# design.net
KiCad netlist of a schematic drawn in EasyEDA
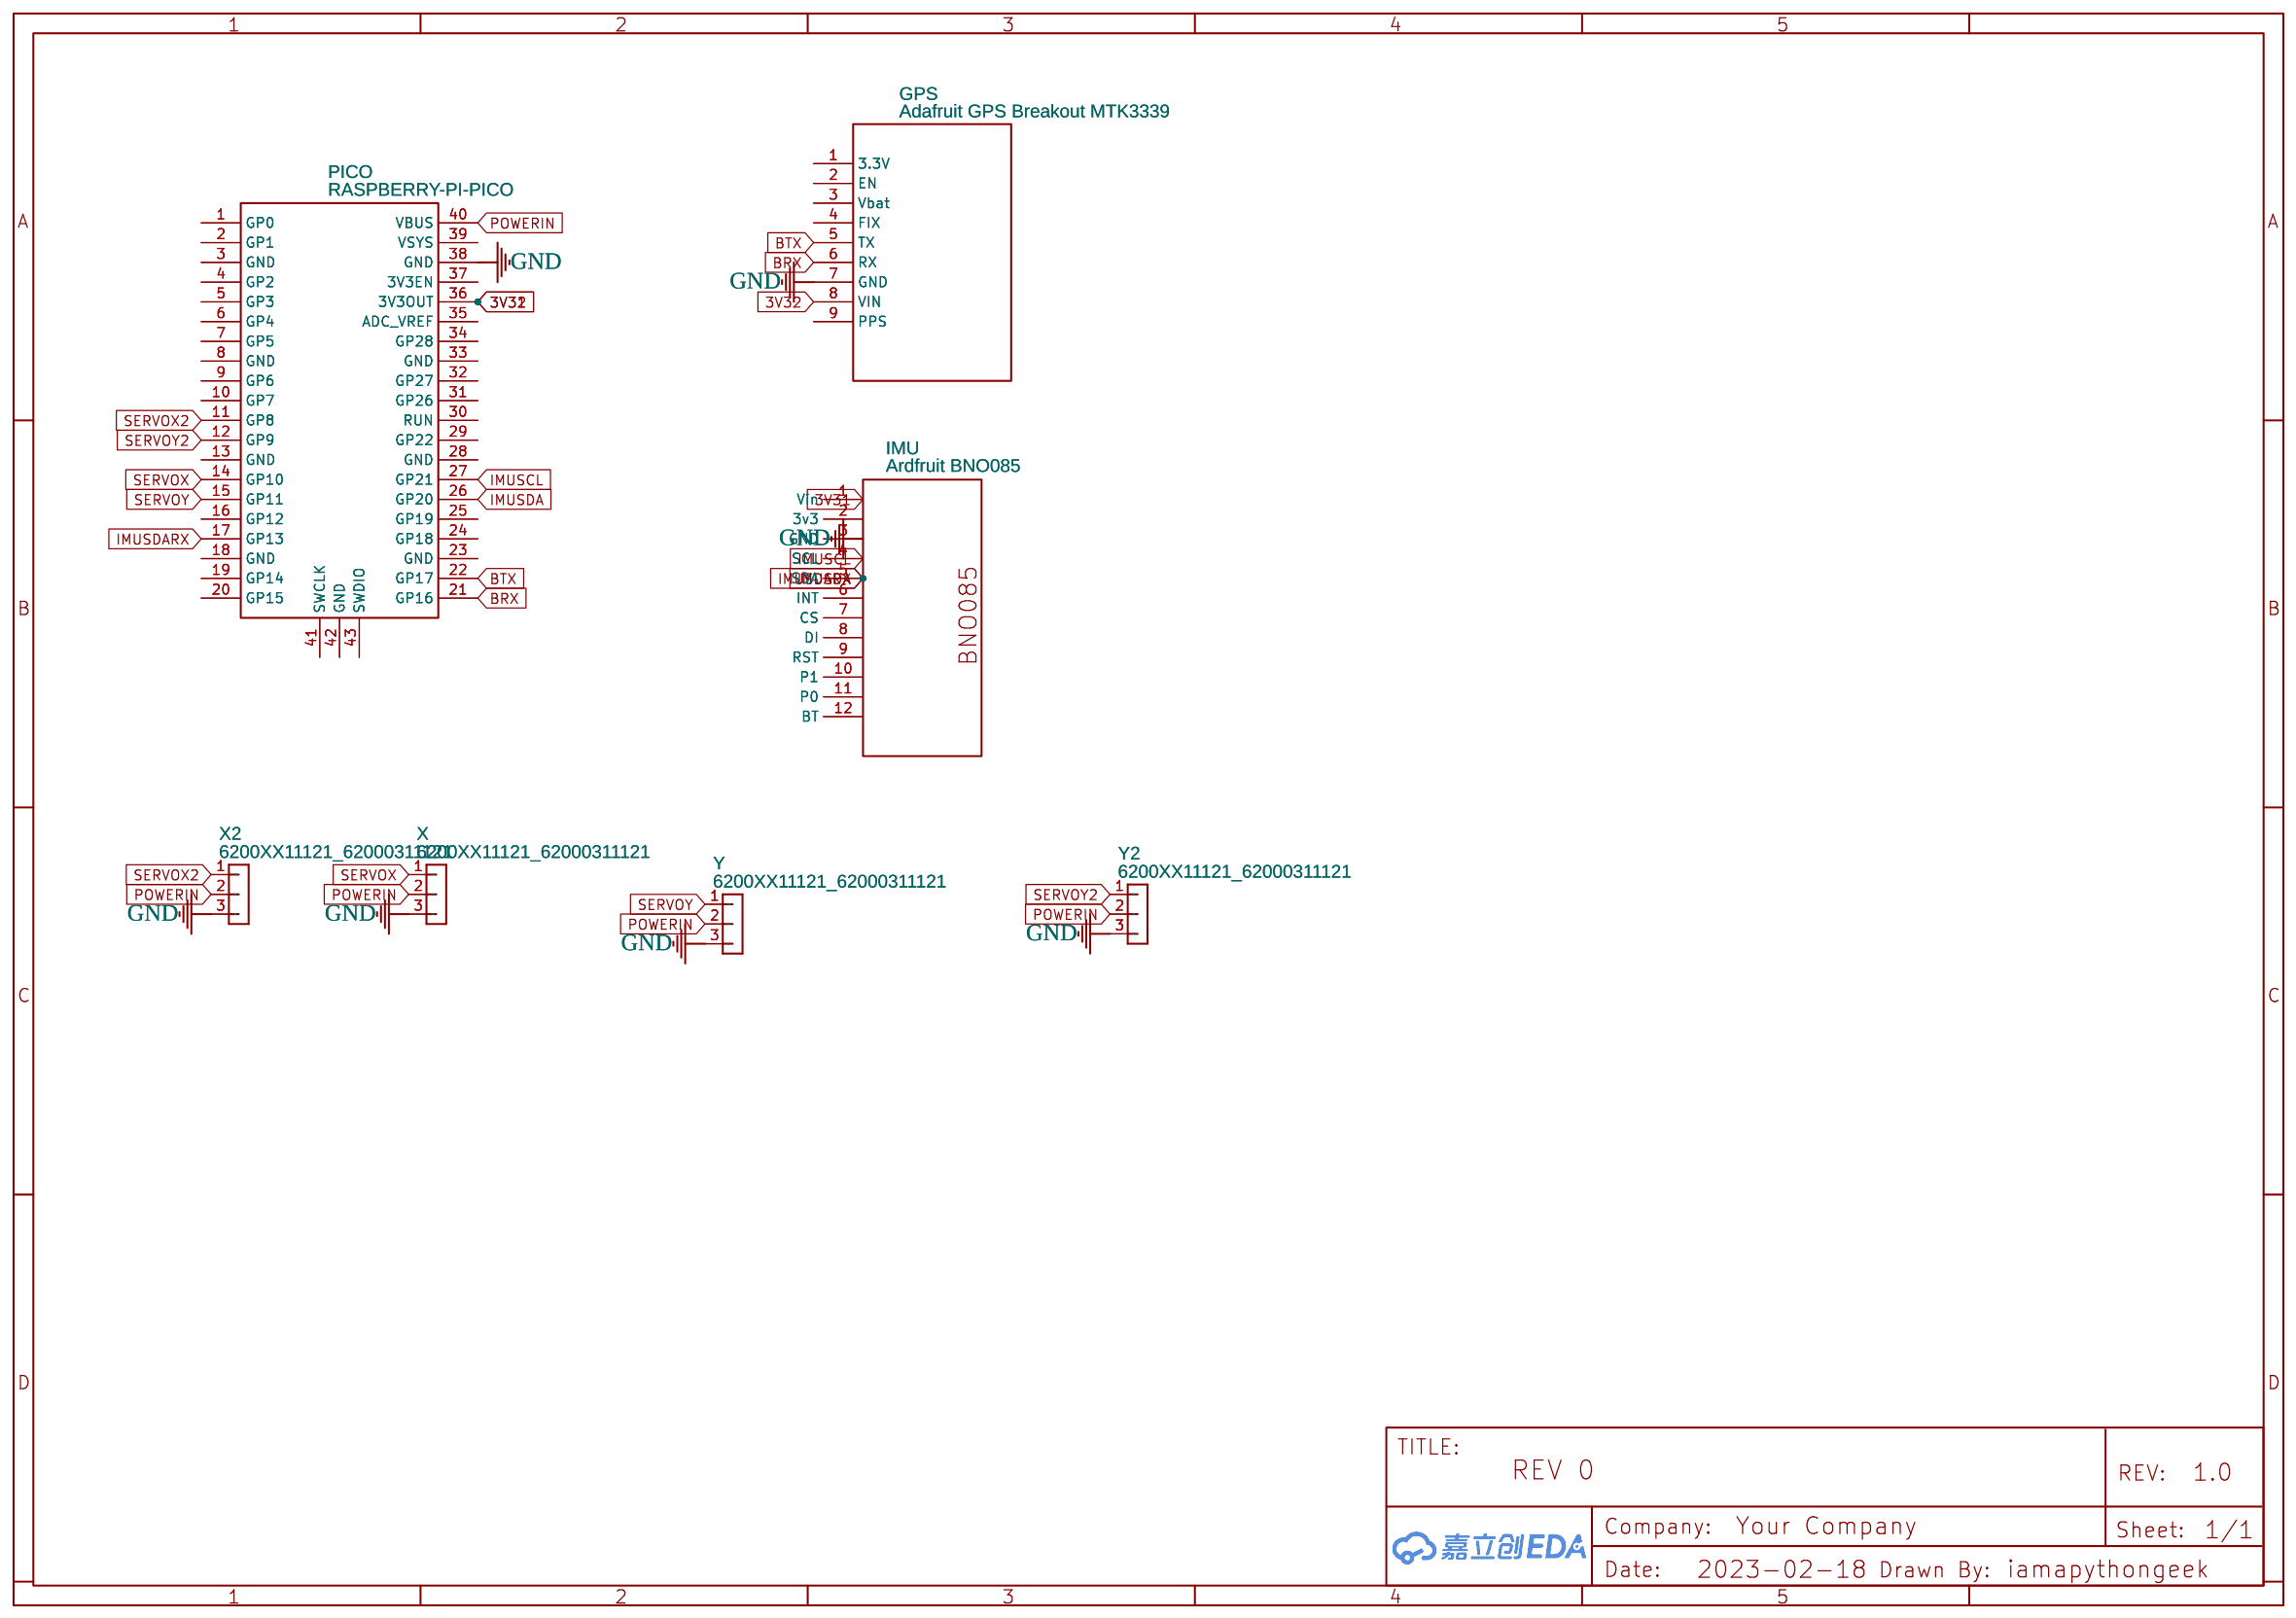
[diagram p0: schematic sheet]

(export (version "E")
  (design (tool "Eeschema 10.0.6"))
  (components
    (comp (ref "GPS")
      (value "Adafruit GPS Breakout MTK3339")
      (libsource (lib "") (part "Adafruit GPS Breakout MTK3339"))
    )
    (comp (ref "IMU") (value "Ardfruit BNO085") (libsource (lib "") (part "Ardfruit BNO085")))
    (comp (ref "PICO") (value "RASPBERRY-PI-PICO") (libsource (lib "") (part "RASPBERRY-PI-PICO")))
    (comp (ref "X") (value "6200XX11121_62000311121") (libsource (lib "") (part "6200XX11121_62000311121")))
    (comp (ref "X2") (value "6200XX11121_62000311121") (libsource (lib "") (part "6200XX11121_62000311121")))
    (comp (ref "Y") (value "6200XX11121_62000311121") (libsource (lib "") (part "6200XX11121_62000311121_1")))
    (comp (ref "Y2")
      (value "6200XX11121_62000311121")
      (libsource (lib "") (part "6200XX11121_62000311121_1"))
    )
  )
  (nets
    (net (code "1") (name "3V31") (class "Default")
      (node (ref "GPS") (pin "8") (pinfunction "VIN_8") (pintype "unspecified"))
      (node (ref "IMU") (pin "1") (pinfunction "Vin_1") (pintype "unspecified"))
      (node (ref "PICO") (pin "36") (pinfunction "3V3OUT_36") (pintype "unspecified"))
    )
    (net (code "2") (name "BRX") (class "Default")
      (node (ref "GPS") (pin "6") (pinfunction "RX_6") (pintype "unspecified"))
      (node (ref "PICO") (pin "21") (pinfunction "GP16_21") (pintype "unspecified"))
    )
    (net (code "3") (name "BTX") (class "Default")
      (node (ref "GPS") (pin "5") (pinfunction "TX_5") (pintype "unspecified"))
      (node (ref "PICO") (pin "22") (pinfunction "GP17_22") (pintype "unspecified"))
    )
    (net (code "4") (name "GND") (class "Default")
      (node (ref "GPS") (pin "7") (pinfunction "GND_7") (pintype "unspecified"))
      (node (ref "IMU") (pin "3") (pinfunction "GND_3") (pintype "unspecified"))
      (node (ref "PICO") (pin "38") (pinfunction "GND_38") (pintype "unspecified"))
      (node (ref "X") (pin "3") (pinfunction "3_3") (pintype "bidirectional"))
      (node (ref "X2") (pin "3") (pinfunction "3_3") (pintype "bidirectional"))
      (node (ref "Y") (pin "3") (pinfunction "3_3") (pintype "bidirectional"))
      (node (ref "Y2") (pin "3") (pinfunction "3_3") (pintype "bidirectional"))
    )
    (net (code "5") (name "IMUSCL") (class "Default")
      (node (ref "IMU") (pin "4") (pinfunction "SCL_4") (pintype "unspecified"))
      (node (ref "PICO") (pin "27") (pinfunction "GP21_27") (pintype "unspecified"))
    )
    (net (code "6") (name "IMUSDA") (class "Default")
      (node (ref "IMU") (pin "5") (pinfunction "SDA_5") (pintype "unspecified"))
      (node (ref "PICO") (pin "17") (pinfunction "GP13_17") (pintype "unspecified"))
      (node (ref "PICO") (pin "26") (pinfunction "GP20_26") (pintype "unspecified"))
    )
    (net (code "7") (name "POWERIN") (class "Default")
      (node (ref "PICO") (pin "40") (pinfunction "VBUS_40") (pintype "unspecified"))
      (node (ref "X") (pin "2") (pinfunction "2_2") (pintype "bidirectional"))
      (node (ref "X2") (pin "2") (pinfunction "2_2") (pintype "bidirectional"))
      (node (ref "Y") (pin "2") (pinfunction "2_2") (pintype "bidirectional"))
      (node (ref "Y2") (pin "2") (pinfunction "2_2") (pintype "bidirectional"))
    )
    (net (code "8") (name "SERVOX") (class "Default")
      (node (ref "PICO") (pin "14") (pinfunction "GP10_14") (pintype "unspecified"))
      (node (ref "X") (pin "1") (pinfunction "1_1") (pintype "bidirectional"))
    )
    (net (code "9") (name "SERVOX2") (class "Default")
      (node (ref "PICO") (pin "11") (pinfunction "GP8_11") (pintype "unspecified"))
      (node (ref "X2") (pin "1") (pinfunction "1_1") (pintype "bidirectional"))
    )
    (net (code "10") (name "SERVOY") (class "Default")
      (node (ref "PICO") (pin "15") (pinfunction "GP11_15") (pintype "unspecified"))
      (node (ref "Y") (pin "1") (pinfunction "1_1") (pintype "bidirectional"))
    )
    (net (code "11") (name "SERVOY2") (class "Default")
      (node (ref "PICO") (pin "12") (pinfunction "GP9_12") (pintype "unspecified"))
      (node (ref "Y2") (pin "1") (pinfunction "1_1") (pintype "bidirectional"))
    )
    (net (code "12") (name "unconnected-(GPS-3.3V-Pad1)") (class "Default")
      (node (ref "GPS") (pin "1") (pinfunction "3.3V_1") (pintype "unspecified"))
    )
    (net (code "13") (name "unconnected-(GPS-EN-Pad2)") (class "Default")
      (node (ref "GPS") (pin "2") (pinfunction "EN_2") (pintype "unspecified"))
    )
    (net (code "14") (name "unconnected-(GPS-FIX-Pad4)") (class "Default")
      (node (ref "GPS") (pin "4") (pinfunction "FIX_4") (pintype "unspecified"))
    )
    (net (code "15") (name "unconnected-(GPS-PPS-Pad9)") (class "Default")
      (node (ref "GPS") (pin "9") (pinfunction "PPS_9") (pintype "unspecified"))
    )
    (net (code "16") (name "unconnected-(GPS-Vbat-Pad3)") (class "Default")
      (node (ref "GPS") (pin "3") (pinfunction "Vbat_3") (pintype "unspecified"))
    )
    (net (code "17") (name "unconnected-(IMU-3v3-Pad2)") (class "Default")
      (node (ref "IMU") (pin "2") (pinfunction "3v3_2") (pintype "unspecified"))
    )
    (net (code "18") (name "unconnected-(IMU-BT-Pad12)") (class "Default")
      (node (ref "IMU") (pin "12") (pinfunction "BT_12") (pintype "unspecified"))
    )
    (net (code "19") (name "unconnected-(IMU-CS-Pad7)") (class "Default")
      (node (ref "IMU") (pin "7") (pinfunction "CS_7") (pintype "unspecified"))
    )
    (net (code "20") (name "unconnected-(IMU-DI-Pad8)") (class "Default")
      (node (ref "IMU") (pin "8") (pinfunction "DI_8") (pintype "unspecified"))
    )
    (net (code "21") (name "unconnected-(IMU-INT-Pad6)") (class "Default")
      (node (ref "IMU") (pin "6") (pinfunction "INT_6") (pintype "unspecified"))
    )
    (net (code "22") (name "unconnected-(IMU-P0-Pad11)") (class "Default")
      (node (ref "IMU") (pin "11") (pinfunction "P0_11") (pintype "unspecified"))
    )
    (net (code "23") (name "unconnected-(IMU-P1-Pad10)") (class "Default")
      (node (ref "IMU") (pin "10") (pinfunction "P1_10") (pintype "unspecified"))
    )
    (net (code "24") (name "unconnected-(IMU-RST-Pad9)") (class "Default")
      (node (ref "IMU") (pin "9") (pinfunction "RST_9") (pintype "unspecified"))
    )
    (net (code "25") (name "unconnected-(PICO-3V3EN-Pad37)") (class "Default")
      (node (ref "PICO") (pin "37") (pinfunction "3V3EN_37") (pintype "unspecified"))
    )
    (net (code "26") (name "unconnected-(PICO-ADC_VREF-Pad35)") (class "Default")
      (node (ref "PICO") (pin "35") (pinfunction "ADC_VREF_35") (pintype "unspecified"))
    )
    (net (code "27") (name "unconnected-(PICO-GND-Pad3)") (class "Default")
      (node (ref "PICO") (pin "3") (pinfunction "GND_3") (pintype "unspecified"))
    )
    (net (code "28") (name "unconnected-(PICO-GND-Pad8)") (class "Default")
      (node (ref "PICO") (pin "8") (pinfunction "GND_8") (pintype "unspecified"))
    )
    (net (code "29") (name "unconnected-(PICO-GND-Pad13)") (class "Default")
      (node (ref "PICO") (pin "13") (pinfunction "GND_13") (pintype "unspecified"))
    )
    (net (code "30") (name "unconnected-(PICO-GND-Pad18)") (class "Default")
      (node (ref "PICO") (pin "18") (pinfunction "GND_18") (pintype "unspecified"))
    )
    (net (code "31") (name "unconnected-(PICO-GND-Pad23)") (class "Default")
      (node (ref "PICO") (pin "23") (pinfunction "GND_23") (pintype "unspecified"))
    )
    (net (code "32") (name "unconnected-(PICO-GND-Pad28)") (class "Default")
      (node (ref "PICO") (pin "28") (pinfunction "GND_28") (pintype "unspecified"))
    )
    (net (code "33") (name "unconnected-(PICO-GND-Pad33)") (class "Default")
      (node (ref "PICO") (pin "33") (pinfunction "GND_33") (pintype "unspecified"))
    )
    (net (code "34") (name "unconnected-(PICO-GND-Pad42)") (class "Default")
      (node (ref "PICO") (pin "42") (pinfunction "GND_42") (pintype "unspecified"))
    )
    (net (code "35") (name "unconnected-(PICO-GP0-Pad1)") (class "Default")
      (node (ref "PICO") (pin "1") (pinfunction "GP0_1") (pintype "unspecified"))
    )
    (net (code "36") (name "unconnected-(PICO-GP1-Pad2)") (class "Default")
      (node (ref "PICO") (pin "2") (pinfunction "GP1_2") (pintype "unspecified"))
    )
    (net (code "37") (name "unconnected-(PICO-GP2-Pad4)") (class "Default")
      (node (ref "PICO") (pin "4") (pinfunction "GP2_4") (pintype "unspecified"))
    )
    (net (code "38") (name "unconnected-(PICO-GP3-Pad5)") (class "Default")
      (node (ref "PICO") (pin "5") (pinfunction "GP3_5") (pintype "unspecified"))
    )
    (net (code "39") (name "unconnected-(PICO-GP4-Pad6)") (class "Default")
      (node (ref "PICO") (pin "6") (pinfunction "GP4_6") (pintype "unspecified"))
    )
    (net (code "40") (name "unconnected-(PICO-GP5-Pad7)") (class "Default")
      (node (ref "PICO") (pin "7") (pinfunction "GP5_7") (pintype "unspecified"))
    )
    (net (code "41") (name "unconnected-(PICO-GP6-Pad9)") (class "Default")
      (node (ref "PICO") (pin "9") (pinfunction "GP6_9") (pintype "unspecified"))
    )
    (net (code "42") (name "unconnected-(PICO-GP7-Pad10)") (class "Default")
      (node (ref "PICO") (pin "10") (pinfunction "GP7_10") (pintype "unspecified"))
    )
    (net (code "43") (name "unconnected-(PICO-GP12-Pad16)") (class "Default")
      (node (ref "PICO") (pin "16") (pinfunction "GP12_16") (pintype "unspecified"))
    )
    (net (code "44") (name "unconnected-(PICO-GP14-Pad19)") (class "Default")
      (node (ref "PICO") (pin "19") (pinfunction "GP14_19") (pintype "unspecified"))
    )
    (net (code "45") (name "unconnected-(PICO-GP15-Pad20)") (class "Default")
      (node (ref "PICO") (pin "20") (pinfunction "GP15_20") (pintype "unspecified"))
    )
    (net (code "46") (name "unconnected-(PICO-GP18-Pad24)") (class "Default")
      (node (ref "PICO") (pin "24") (pinfunction "GP18_24") (pintype "unspecified"))
    )
    (net (code "47") (name "unconnected-(PICO-GP19-Pad25)") (class "Default")
      (node (ref "PICO") (pin "25") (pinfunction "GP19_25") (pintype "unspecified"))
    )
    (net (code "48") (name "unconnected-(PICO-GP22-Pad29)") (class "Default")
      (node (ref "PICO") (pin "29") (pinfunction "GP22_29") (pintype "unspecified"))
    )
    (net (code "49") (name "unconnected-(PICO-GP26-Pad31)") (class "Default")
      (node (ref "PICO") (pin "31") (pinfunction "GP26_31") (pintype "unspecified"))
    )
    (net (code "50") (name "unconnected-(PICO-GP27-Pad32)") (class "Default")
      (node (ref "PICO") (pin "32") (pinfunction "GP27_32") (pintype "unspecified"))
    )
    (net (code "51") (name "unconnected-(PICO-GP28-Pad34)") (class "Default")
      (node (ref "PICO") (pin "34") (pinfunction "GP28_34") (pintype "unspecified"))
    )
    (net (code "52") (name "unconnected-(PICO-RUN-Pad30)") (class "Default")
      (node (ref "PICO") (pin "30") (pinfunction "RUN_30") (pintype "unspecified"))
    )
    (net (code "53") (name "unconnected-(PICO-SWCLK-Pad41)") (class "Default")
      (node (ref "PICO") (pin "41") (pinfunction "SWCLK_41") (pintype "unspecified"))
    )
    (net (code "54") (name "unconnected-(PICO-SWDIO-Pad43)") (class "Default")
      (node (ref "PICO") (pin "43") (pinfunction "SWDIO_43") (pintype "unspecified"))
    )
    (net (code "55") (name "unconnected-(PICO-VSYS-Pad39)") (class "Default")
      (node (ref "PICO") (pin "39") (pinfunction "VSYS_39") (pintype "unspecified"))
    )
  )
)
